# Connectors.net
KiCad netlist of a schematic drawn in Altium Designer
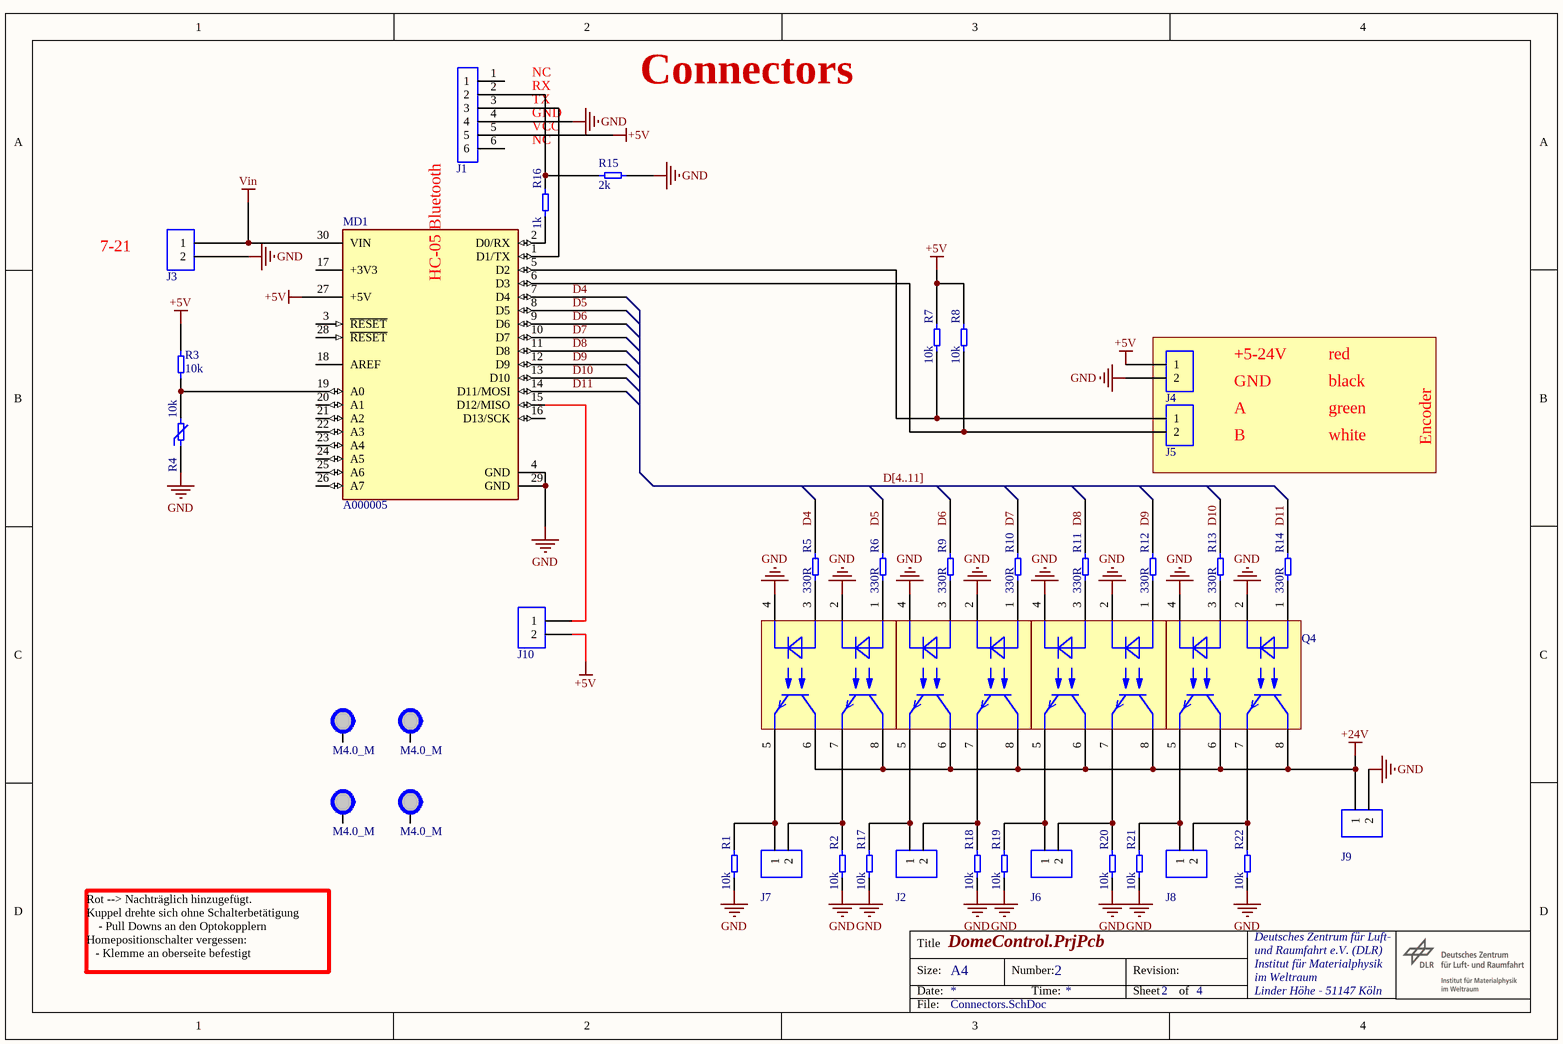
[diagram p0: Connectors.SchDoc]

(export (version "E")
  (design (tool "Eeschema 10.0.6"))
  (components
    (comp (ref "Drill1")
      (value "M4.0_M")
      (footprint "M4.0_M")
      (fields (field (name ".CHECKED PCB") "RF") (field (name ".CHECKED SCH") "RF"))
      (libsource (lib "Drills") (part "Drill"))
    )
    (comp (ref "Drill2")
      (value "M4.0_M")
      (footprint "M4.0_M")
      (fields (field (name ".CHECKED PCB") "RF") (field (name ".CHECKED SCH") "RF"))
      (libsource (lib "Drills") (part "Drill"))
    )
    (comp (ref "Drill3")
      (value "M4.0_M")
      (footprint "M4.0_M")
      (fields (field (name ".CHECKED PCB") "RF") (field (name ".CHECKED SCH") "RF"))
      (libsource (lib "Drills") (part "Drill"))
    )
    (comp (ref "Drill4")
      (value "M4.0_M")
      (footprint "M4.0_M")
      (fields (field (name ".CHECKED PCB") "RF") (field (name ".CHECKED SCH") "RF"))
      (libsource (lib "Drills") (part "Drill"))
    )
    (comp (ref "J1")
      (value "61300611121")
      (footprint "6P Stiftleiste 2,54")
      (fields
        (field (name "RS PART NUMBER") "172-5168")
        (field (name ".CHECKED PCB") "RF")
        (field (name ".CHECKED SCH") "RF")
      )
      (libsource (lib "EigenDefault") (part "6P Stiftleiste 2,54"))
    )
    (comp (ref "J2")
      (value "PM_5.08_3_90_3.5_SW_-176052000")
      (footprint "MKDSN 5,08/2 2,5")
      (description "间距5.08mm 2pin 10A 300V 可拼接 螺钉式 直插 配线24-14AWG(0.2-2.5)mm²")
      (fields
        (field (name "MANUFACTURER") "Phoenix Contact")
        (field (name "MANUFACTURER PART NUMBER") "1888687")
        (field (name ".CHECKED PCB") "PS")
        (field (name ".CHECKED SCH") "PS")
      )
      (libsource (lib "Phoenix Contact") (part "MKDSN 5,08/2 2,5"))
    )
    (comp (ref "J3")
      (value "PM_5.08_3_90_3.5_SW_-176052000")
      (footprint "MKDSN 5,08/2 2,5")
      (description "间距5.08mm 2pin 10A 300V 可拼接 螺钉式 直插 配线24-14AWG(0.2-2.5)mm²")
      (fields
        (field (name "MANUFACTURER") "Phoenix Contact")
        (field (name "MANUFACTURER PART NUMBER") "1888687")
        (field (name ".CHECKED PCB") "PS")
        (field (name ".CHECKED SCH") "PS")
      )
      (libsource (lib "Phoenix Contact") (part "MKDSN 5,08/2 2,5"))
    )
    (comp (ref "J4")
      (value "PM_5.08_3_90_3.5_SW_-176052000")
      (footprint "MKDSN 5,08/2 2,5")
      (description "间距5.08mm 2pin 10A 300V 可拼接 螺钉式 直插 配线24-14AWG(0.2-2.5)mm²")
      (fields
        (field (name "MANUFACTURER") "Phoenix Contact")
        (field (name "MANUFACTURER PART NUMBER") "1888687")
        (field (name ".CHECKED PCB") "PS")
        (field (name ".CHECKED SCH") "PS")
      )
      (libsource (lib "Phoenix Contact") (part "MKDSN 5,08/2 2,5"))
    )
    (comp (ref "J5")
      (value "PM_5.08_3_90_3.5_SW_-176052000")
      (footprint "MKDSN 5,08/2 2,5")
      (description "间距5.08mm 2pin 10A 300V 可拼接 螺钉式 直插 配线24-14AWG(0.2-2.5)mm²")
      (fields
        (field (name "MANUFACTURER") "Phoenix Contact")
        (field (name "MANUFACTURER PART NUMBER") "1888687")
        (field (name ".CHECKED PCB") "PS")
        (field (name ".CHECKED SCH") "PS")
      )
      (libsource (lib "Phoenix Contact") (part "MKDSN 5,08/2 2,5"))
    )
    (comp (ref "J6")
      (value "PM_5.08_3_90_3.5_SW_-176052000")
      (footprint "MKDSN 5,08/2 2,5")
      (description "间距5.08mm 2pin 10A 300V 可拼接 螺钉式 直插 配线24-14AWG(0.2-2.5)mm²")
      (fields
        (field (name "MANUFACTURER") "Phoenix Contact")
        (field (name "MANUFACTURER PART NUMBER") "1888687")
        (field (name ".CHECKED PCB") "PS")
        (field (name ".CHECKED SCH") "PS")
      )
      (libsource (lib "Phoenix Contact") (part "MKDSN 5,08/2 2,5"))
    )
    (comp (ref "J7")
      (value "PM_5.08_3_90_3.5_SW_-176052000")
      (footprint "MKDSN 5,08/2 2,5")
      (description "间距5.08mm 2pin 10A 300V 可拼接 螺钉式 直插 配线24-14AWG(0.2-2.5)mm²")
      (fields
        (field (name "MANUFACTURER") "Phoenix Contact")
        (field (name "MANUFACTURER PART NUMBER") "1888687")
        (field (name ".CHECKED PCB") "PS")
        (field (name ".CHECKED SCH") "PS")
      )
      (libsource (lib "Phoenix Contact") (part "MKDSN 5,08/2 2,5"))
    )
    (comp (ref "J8")
      (value "PM_5.08_3_90_3.5_SW_-176052000")
      (footprint "MKDSN 5,08/2 2,5")
      (description "间距5.08mm 2pin 10A 300V 可拼接 螺钉式 直插 配线24-14AWG(0.2-2.5)mm²")
      (fields
        (field (name "MANUFACTURER") "Phoenix Contact")
        (field (name "MANUFACTURER PART NUMBER") "1888687")
        (field (name ".CHECKED PCB") "PS")
        (field (name ".CHECKED SCH") "PS")
      )
      (libsource (lib "Phoenix Contact") (part "MKDSN 5,08/2 2,5"))
    )
    (comp (ref "J9")
      (value "PM_5.08_3_90_3.5_SW_-176052000")
      (footprint "MKDSN 5,08/2 2,5")
      (description "间距5.08mm 2pin 10A 300V 可拼接 螺钉式 直插 配线24-14AWG(0.2-2.5)mm²")
      (fields
        (field (name "MANUFACTURER") "Phoenix Contact")
        (field (name "MANUFACTURER PART NUMBER") "1888687")
        (field (name ".CHECKED PCB") "PS")
        (field (name ".CHECKED SCH") "PS")
      )
      (libsource (lib "Phoenix Contact") (part "MKDSN 5,08/2 2,5"))
    )
    (comp (ref "J10")
      (value "PM_5.08_3_90_3.5_SW_-176052000")
      (footprint "MKDSN 5,08/2 2,5")
      (description "间距5.08mm 2pin 10A 300V 可拼接 螺钉式 直插 配线24-14AWG(0.2-2.5)mm²")
      (fields
        (field (name "MANUFACTURER") "Phoenix Contact")
        (field (name "MANUFACTURER PART NUMBER") "1888687")
        (field (name ".CHECKED PCB") "PS")
        (field (name ".CHECKED SCH") "PS")
      )
      (libsource (lib "Phoenix Contact") (part "MKDSN 5,08/2 2,5"))
    )
    (comp (ref "MD1")
      (value "A000005")
      (footprint "FP-A000005-MFG")
      (description "ARDUINO NANO ATMEGA328 EVAL BRD")
      (libsource (lib "Altium Content Vault") (part "d190c066e99afd1c6882cf92e11b2cc"))
    )
    (comp (ref "Q1")
      (value "140827180010")
      (footprint "WL-OCPT_DIP8_Standard")
      (description "140827180010 WL-OCPT - Optocoupler Phototransistor")
      (libsource (lib "Altium Content Vault") (part "Optocoupler Phototransistor_DC_2 Channel"))
    )
    (comp (ref "Q2")
      (value "140827180010")
      (footprint "WL-OCPT_DIP8_Standard")
      (description "140827180010 WL-OCPT - Optocoupler Phototransistor")
      (libsource (lib "Altium Content Vault") (part "Optocoupler Phototransistor_DC_2 Channel"))
    )
    (comp (ref "Q3")
      (value "140827180010")
      (footprint "WL-OCPT_DIP8_Standard")
      (description "140827180010 WL-OCPT - Optocoupler Phototransistor")
      (libsource (lib "Altium Content Vault") (part "Optocoupler Phototransistor_DC_2 Channel"))
    )
    (comp (ref "Q4")
      (value "140827180010")
      (footprint "WL-OCPT_DIP8_Standard")
      (description "140827180010 WL-OCPT - Optocoupler Phototransistor")
      (libsource (lib "Altium Content Vault") (part "Optocoupler Phototransistor_DC_2 Channel"))
    )
    (comp (ref "R1")
      (value "10k")
      (footprint "Passive Bauelemente:laser AXIAL-0.5")
      (fields (field (name ".CHECKED PCB") "PS") (field (name ".CHECKED SCH") "PS"))
      (libsource (lib "Passive Bauelemente") (part "R-THT"))
    )
    (comp (ref "R2")
      (value "10k")
      (footprint "Passive Bauelemente:laser AXIAL-0.5")
      (fields (field (name ".CHECKED PCB") "PS") (field (name ".CHECKED SCH") "PS"))
      (libsource (lib "Passive Bauelemente") (part "R-THT"))
    )
    (comp (ref "R3")
      (value "10k")
      (footprint "Passive Bauelemente:laser AXIAL-0.5")
      (fields (field (name ".CHECKED PCB") "PS") (field (name ".CHECKED SCH") "PS"))
      (libsource (lib "Passive Bauelemente") (part "R-THT"))
    )
    (comp (ref "R4")
      (value "10k")
      (footprint "Passive Bauelemente:FP-103AT-2-MFG")
      (description "Thermistor NTC 10KOhm 1% 2-Pin\r\n103AT-2")
      (fields (field (name "TOLERANCE") "1%") (field (name "MANUFACTURER") "Semitec"))
      (libsource (lib "Passive Bauelemente") (part "R_Thermistor 2.54"))
    )
    (comp (ref "R5")
      (value "330R")
      (footprint "Passive Bauelemente:laser AXIAL-0.5")
      (fields (field (name ".CHECKED PCB") "PS") (field (name ".CHECKED SCH") "PS"))
      (libsource (lib "Passive Bauelemente") (part "R-THT"))
    )
    (comp (ref "R6")
      (value "330R")
      (footprint "Passive Bauelemente:laser AXIAL-0.5")
      (fields (field (name ".CHECKED PCB") "PS") (field (name ".CHECKED SCH") "PS"))
      (libsource (lib "Passive Bauelemente") (part "R-THT"))
    )
    (comp (ref "R7")
      (value "10k")
      (footprint "Passive Bauelemente:laser AXIAL-0.5")
      (fields (field (name ".CHECKED PCB") "PS") (field (name ".CHECKED SCH") "PS"))
      (libsource (lib "Passive Bauelemente") (part "R-THT"))
    )
    (comp (ref "R8")
      (value "10k")
      (footprint "Passive Bauelemente:laser AXIAL-0.5")
      (fields (field (name ".CHECKED PCB") "PS") (field (name ".CHECKED SCH") "PS"))
      (libsource (lib "Passive Bauelemente") (part "R-THT"))
    )
    (comp (ref "R9")
      (value "330R")
      (footprint "Passive Bauelemente:laser AXIAL-0.5")
      (fields (field (name ".CHECKED PCB") "PS") (field (name ".CHECKED SCH") "PS"))
      (libsource (lib "Passive Bauelemente") (part "R-THT"))
    )
    (comp (ref "R10")
      (value "330R")
      (footprint "Passive Bauelemente:laser AXIAL-0.5")
      (fields (field (name ".CHECKED PCB") "PS") (field (name ".CHECKED SCH") "PS"))
      (libsource (lib "Passive Bauelemente") (part "R-THT"))
    )
    (comp (ref "R11")
      (value "330R")
      (footprint "Passive Bauelemente:laser AXIAL-0.5")
      (fields (field (name ".CHECKED PCB") "PS") (field (name ".CHECKED SCH") "PS"))
      (libsource (lib "Passive Bauelemente") (part "R-THT"))
    )
    (comp (ref "R12")
      (value "330R")
      (footprint "Passive Bauelemente:laser AXIAL-0.5")
      (fields (field (name ".CHECKED PCB") "PS") (field (name ".CHECKED SCH") "PS"))
      (libsource (lib "Passive Bauelemente") (part "R-THT"))
    )
    (comp (ref "R13")
      (value "330R")
      (footprint "Passive Bauelemente:laser AXIAL-0.5")
      (fields (field (name ".CHECKED PCB") "PS") (field (name ".CHECKED SCH") "PS"))
      (libsource (lib "Passive Bauelemente") (part "R-THT"))
    )
    (comp (ref "R14")
      (value "330R")
      (footprint "Passive Bauelemente:laser AXIAL-0.5")
      (fields (field (name ".CHECKED PCB") "PS") (field (name ".CHECKED SCH") "PS"))
      (libsource (lib "Passive Bauelemente") (part "R-THT"))
    )
    (comp (ref "R15")
      (value "2k")
      (footprint "Passive Bauelemente:laser AXIAL-0.5")
      (fields (field (name ".CHECKED PCB") "PS") (field (name ".CHECKED SCH") "PS"))
      (libsource (lib "Passive Bauelemente") (part "R-THT"))
    )
    (comp (ref "R16")
      (value "1k")
      (footprint "Passive Bauelemente:laser AXIAL-0.5")
      (fields (field (name ".CHECKED PCB") "PS") (field (name ".CHECKED SCH") "PS"))
      (libsource (lib "Passive Bauelemente") (part "R-THT"))
    )
    (comp (ref "R17")
      (value "10k")
      (footprint "Passive Bauelemente:laser AXIAL-0.5")
      (fields (field (name ".CHECKED PCB") "PS") (field (name ".CHECKED SCH") "PS"))
      (libsource (lib "Passive Bauelemente") (part "R-THT"))
    )
    (comp (ref "R18")
      (value "10k")
      (footprint "Passive Bauelemente:laser AXIAL-0.5")
      (fields (field (name ".CHECKED PCB") "PS") (field (name ".CHECKED SCH") "PS"))
      (libsource (lib "Passive Bauelemente") (part "R-THT"))
    )
    (comp (ref "R19")
      (value "10k")
      (footprint "Passive Bauelemente:laser AXIAL-0.5")
      (fields (field (name ".CHECKED PCB") "PS") (field (name ".CHECKED SCH") "PS"))
      (libsource (lib "Passive Bauelemente") (part "R-THT"))
    )
    (comp (ref "R20")
      (value "10k")
      (footprint "Passive Bauelemente:laser AXIAL-0.5")
      (fields (field (name ".CHECKED PCB") "PS") (field (name ".CHECKED SCH") "PS"))
      (libsource (lib "Passive Bauelemente") (part "R-THT"))
    )
    (comp (ref "R21")
      (value "10k")
      (footprint "Passive Bauelemente:laser AXIAL-0.5")
      (fields (field (name ".CHECKED PCB") "PS") (field (name ".CHECKED SCH") "PS"))
      (libsource (lib "Passive Bauelemente") (part "R-THT"))
    )
    (comp (ref "R22")
      (value "10k")
      (footprint "Passive Bauelemente:laser AXIAL-0.5")
      (fields (field (name ".CHECKED PCB") "PS") (field (name ".CHECKED SCH") "PS"))
      (libsource (lib "Passive Bauelemente") (part "R-THT"))
    )
  )
  (nets
    (net (code "1") (name "+5V") (class "Default")
      (node (ref "J1") (pin "5") (pinfunction "5_5") (pintype "passive"))
      (node (ref "J10") (pin "2") (pinfunction "2_2") (pintype "passive"))
      (node (ref "J4") (pin "1") (pinfunction "1_1") (pintype "passive"))
      (node (ref "MD1") (pin "27") (pinfunction "+5V_27") (pintype "power_in"))
      (node (ref "R3") (pin "2") (pinfunction "2_2") (pintype "passive"))
      (node (ref "R7") (pin "1") (pinfunction "1_1") (pintype "passive"))
      (node (ref "R8") (pin "1") (pinfunction "1_1") (pintype "passive"))
    )
    (net (code "2") (name "+24V") (class "Default")
      (node (ref "J9") (pin "1") (pinfunction "1_1") (pintype "passive"))
      (node (ref "Q1") (pin "6") (pinfunction "Collector_6") (pintype "passive"))
      (node (ref "Q1") (pin "8") (pinfunction "Collector_8") (pintype "passive"))
      (node (ref "Q2") (pin "6") (pinfunction "Collector_6") (pintype "passive"))
      (node (ref "Q2") (pin "8") (pinfunction "Collector_8") (pintype "passive"))
      (node (ref "Q3") (pin "6") (pinfunction "Collector_6") (pintype "passive"))
      (node (ref "Q3") (pin "8") (pinfunction "Collector_8") (pintype "passive"))
      (node (ref "Q4") (pin "6") (pinfunction "Collector_6") (pintype "passive"))
      (node (ref "Q4") (pin "8") (pinfunction "Collector_8") (pintype "passive"))
    )
    (net (code "3") (name "/D4") (class "Default")
      (node (ref "MD1") (pin "7") (pinfunction "D4_7") (pintype "bidirectional"))
      (node (ref "R5") (pin "1") (pinfunction "1_1") (pintype "passive"))
    )
    (net (code "4") (name "/D5") (class "Default")
      (node (ref "MD1") (pin "8") (pinfunction "D5_8") (pintype "bidirectional"))
      (node (ref "R6") (pin "1") (pinfunction "1_1") (pintype "passive"))
    )
    (net (code "5") (name "/D6") (class "Default")
      (node (ref "MD1") (pin "9") (pinfunction "D6_9") (pintype "bidirectional"))
      (node (ref "R9") (pin "1") (pinfunction "1_1") (pintype "passive"))
    )
    (net (code "6") (name "/D7") (class "Default")
      (node (ref "MD1") (pin "10") (pinfunction "D7_10") (pintype "bidirectional"))
      (node (ref "R10") (pin "1") (pinfunction "1_1") (pintype "passive"))
    )
    (net (code "7") (name "/D8") (class "Default")
      (node (ref "MD1") (pin "11") (pinfunction "D8_11") (pintype "bidirectional"))
      (node (ref "R11") (pin "1") (pinfunction "1_1") (pintype "passive"))
    )
    (net (code "8") (name "/D9") (class "Default")
      (node (ref "MD1") (pin "12") (pinfunction "D9_12") (pintype "bidirectional"))
      (node (ref "R12") (pin "1") (pinfunction "1_1") (pintype "passive"))
    )
    (net (code "9") (name "/D10") (class "Default")
      (node (ref "MD1") (pin "13") (pinfunction "D10_13") (pintype "bidirectional"))
      (node (ref "R13") (pin "1") (pinfunction "1_1") (pintype "passive"))
    )
    (net (code "10") (name "/D11") (class "Default")
      (node (ref "MD1") (pin "14") (pinfunction "D11/MOSI_14") (pintype "bidirectional"))
      (node (ref "R14") (pin "1") (pinfunction "1_1") (pintype "passive"))
    )
    (net (code "12") (name "GND") (class "Default")
      (node (ref "J1") (pin "4") (pinfunction "4_4") (pintype "passive"))
      (node (ref "J3") (pin "2") (pinfunction "2_2") (pintype "passive"))
      (node (ref "J4") (pin "2") (pinfunction "2_2") (pintype "passive"))
      (node (ref "J9") (pin "2") (pinfunction "2_2") (pintype "passive"))
      (node (ref "MD1") (pin "29") (pinfunction "GND_29") (pintype "power_in"))
      (node (ref "MD1") (pin "4") (pinfunction "GND_4") (pintype "power_in"))
      (node (ref "Q1") (pin "2") (pinfunction "Cathode_2") (pintype "passive"))
      (node (ref "Q1") (pin "4") (pinfunction "Cathode_4") (pintype "passive"))
      (node (ref "Q2") (pin "2") (pinfunction "Cathode_2") (pintype "passive"))
      (node (ref "Q2") (pin "4") (pinfunction "Cathode_4") (pintype "passive"))
      (node (ref "Q3") (pin "2") (pinfunction "Cathode_2") (pintype "passive"))
      (node (ref "Q3") (pin "4") (pinfunction "Cathode_4") (pintype "passive"))
      (node (ref "Q4") (pin "2") (pinfunction "Cathode_2") (pintype "passive"))
      (node (ref "Q4") (pin "4") (pinfunction "Cathode_4") (pintype "passive"))
      (node (ref "R1") (pin "2") (pinfunction "2_2") (pintype "passive"))
      (node (ref "R15") (pin "2") (pinfunction "2_2") (pintype "passive"))
      (node (ref "R17") (pin "2") (pinfunction "2_2") (pintype "passive"))
      (node (ref "R18") (pin "2") (pinfunction "2_2") (pintype "passive"))
      (node (ref "R19") (pin "2") (pinfunction "2_2") (pintype "passive"))
      (node (ref "R2") (pin "2") (pinfunction "2_2") (pintype "passive"))
      (node (ref "R20") (pin "2") (pinfunction "2_2") (pintype "passive"))
      (node (ref "R21") (pin "2") (pinfunction "2_2") (pintype "passive"))
      (node (ref "R22") (pin "2") (pinfunction "2_2") (pintype "passive"))
      (node (ref "R4") (pin "1") (pinfunction "1_1") (pintype "passive"))
    )
    (net (code "13") (name "Net-(J1-Pad2)") (class "Default")
      (node (ref "J1") (pin "2") (pinfunction "2_2") (pintype "passive"))
      (node (ref "R15") (pin "1") (pinfunction "1_1") (pintype "passive"))
      (node (ref "R16") (pin "2") (pinfunction "2_2") (pintype "passive"))
    )
    (net (code "14") (name "Net-(J2-Pad1)") (class "Default")
      (node (ref "J2") (pin "1") (pinfunction "1_1") (pintype "passive"))
      (node (ref "Q2") (pin "5") (pinfunction "Emitter_5") (pintype "passive"))
      (node (ref "R17") (pin "1") (pinfunction "1_1") (pintype "passive"))
    )
    (net (code "15") (name "Net-(J2-Pad2)") (class "Default")
      (node (ref "J2") (pin "2") (pinfunction "2_2") (pintype "passive"))
      (node (ref "Q2") (pin "7") (pinfunction "Emitter_7") (pintype "passive"))
      (node (ref "R18") (pin "1") (pinfunction "1_1") (pintype "passive"))
    )
    (net (code "16") (name "Net-(J6-Pad1)") (class "Default")
      (node (ref "J6") (pin "1") (pinfunction "1_1") (pintype "passive"))
      (node (ref "Q3") (pin "5") (pinfunction "Emitter_5") (pintype "passive"))
      (node (ref "R19") (pin "1") (pinfunction "1_1") (pintype "passive"))
    )
    (net (code "17") (name "Net-(J6-Pad2)") (class "Default")
      (node (ref "J6") (pin "2") (pinfunction "2_2") (pintype "passive"))
      (node (ref "Q3") (pin "7") (pinfunction "Emitter_7") (pintype "passive"))
      (node (ref "R20") (pin "1") (pinfunction "1_1") (pintype "passive"))
    )
    (net (code "18") (name "Net-(J7-Pad1)") (class "Default")
      (node (ref "J7") (pin "1") (pinfunction "1_1") (pintype "passive"))
      (node (ref "Q1") (pin "5") (pinfunction "Emitter_5") (pintype "passive"))
      (node (ref "R1") (pin "1") (pinfunction "1_1") (pintype "passive"))
    )
    (net (code "19") (name "Net-(J7-Pad2)") (class "Default")
      (node (ref "J7") (pin "2") (pinfunction "2_2") (pintype "passive"))
      (node (ref "Q1") (pin "7") (pinfunction "Emitter_7") (pintype "passive"))
      (node (ref "R2") (pin "1") (pinfunction "1_1") (pintype "passive"))
    )
    (net (code "20") (name "Net-(J8-Pad1)") (class "Default")
      (node (ref "J8") (pin "1") (pinfunction "1_1") (pintype "passive"))
      (node (ref "Q4") (pin "5") (pinfunction "Emitter_5") (pintype "passive"))
      (node (ref "R21") (pin "1") (pinfunction "1_1") (pintype "passive"))
    )
    (net (code "21") (name "Net-(J8-Pad2)") (class "Default")
      (node (ref "J8") (pin "2") (pinfunction "2_2") (pintype "passive"))
      (node (ref "Q4") (pin "7") (pinfunction "Emitter_7") (pintype "passive"))
      (node (ref "R22") (pin "1") (pinfunction "1_1") (pintype "passive"))
    )
    (net (code "22") (name "Net-(MD1-A0)") (class "Default")
      (node (ref "MD1") (pin "19") (pinfunction "A0_19") (pintype "bidirectional"))
      (node (ref "R3") (pin "1") (pinfunction "1_1") (pintype "passive"))
      (node (ref "R4") (pin "2") (pinfunction "2_2") (pintype "passive"))
    )
    (net (code "23") (name "Net-(MD1-D0{slash}RX)") (class "Default")
      (node (ref "MD1") (pin "2") (pinfunction "D0/RX_2") (pintype "bidirectional"))
      (node (ref "R16") (pin "1") (pinfunction "1_1") (pintype "passive"))
    )
    (net (code "24") (name "Net-(MD1-D1{slash}TX)") (class "Default")
      (node (ref "J1") (pin "3") (pinfunction "3_3") (pintype "passive"))
      (node (ref "MD1") (pin "1") (pinfunction "D1/TX_1") (pintype "bidirectional"))
    )
    (net (code "25") (name "Net-(MD1-D2)") (class "Default")
      (node (ref "J5") (pin "1") (pinfunction "1_1") (pintype "passive"))
      (node (ref "MD1") (pin "5") (pinfunction "D2_5") (pintype "bidirectional"))
      (node (ref "R7") (pin "2") (pinfunction "2_2") (pintype "passive"))
    )
    (net (code "26") (name "Net-(MD1-D3)") (class "Default")
      (node (ref "J5") (pin "2") (pinfunction "2_2") (pintype "passive"))
      (node (ref "MD1") (pin "6") (pinfunction "D3_6") (pintype "bidirectional"))
      (node (ref "R8") (pin "2") (pinfunction "2_2") (pintype "passive"))
    )
    (net (code "27") (name "Net-(MD1-D12{slash}MISO)") (class "Default")
      (node (ref "J10") (pin "1") (pinfunction "1_1") (pintype "passive"))
      (node (ref "MD1") (pin "15") (pinfunction "D12/MISO_15") (pintype "bidirectional"))
    )
    (net (code "28") (name "Net-(Q1-Anode-Pad1)") (class "Default")
      (node (ref "Q1") (pin "1") (pinfunction "Anode_1") (pintype "passive"))
      (node (ref "R6") (pin "2") (pinfunction "2_2") (pintype "passive"))
    )
    (net (code "29") (name "Net-(Q1-Anode-Pad3)") (class "Default")
      (node (ref "Q1") (pin "3") (pinfunction "Anode_3") (pintype "passive"))
      (node (ref "R5") (pin "2") (pinfunction "2_2") (pintype "passive"))
    )
    (net (code "30") (name "Net-(Q2-Anode-Pad1)") (class "Default")
      (node (ref "Q2") (pin "1") (pinfunction "Anode_1") (pintype "passive"))
      (node (ref "R10") (pin "2") (pinfunction "2_2") (pintype "passive"))
    )
    (net (code "31") (name "Net-(Q2-Anode-Pad3)") (class "Default")
      (node (ref "Q2") (pin "3") (pinfunction "Anode_3") (pintype "passive"))
      (node (ref "R9") (pin "2") (pinfunction "2_2") (pintype "passive"))
    )
    (net (code "32") (name "Net-(Q3-Anode-Pad1)") (class "Default")
      (node (ref "Q3") (pin "1") (pinfunction "Anode_1") (pintype "passive"))
      (node (ref "R12") (pin "2") (pinfunction "2_2") (pintype "passive"))
    )
    (net (code "33") (name "Net-(Q3-Anode-Pad3)") (class "Default")
      (node (ref "Q3") (pin "3") (pinfunction "Anode_3") (pintype "passive"))
      (node (ref "R11") (pin "2") (pinfunction "2_2") (pintype "passive"))
    )
    (net (code "34") (name "Net-(Q4-Anode-Pad1)") (class "Default")
      (node (ref "Q4") (pin "1") (pinfunction "Anode_1") (pintype "passive"))
      (node (ref "R14") (pin "2") (pinfunction "2_2") (pintype "passive"))
    )
    (net (code "35") (name "Net-(Q4-Anode-Pad3)") (class "Default")
      (node (ref "Q4") (pin "3") (pinfunction "Anode_3") (pintype "passive"))
      (node (ref "R13") (pin "2") (pinfunction "2_2") (pintype "passive"))
    )
    (net (code "36") (name "Vin") (class "Default")
      (node (ref "J3") (pin "1") (pinfunction "1_1") (pintype "passive"))
      (node (ref "MD1") (pin "30") (pinfunction "VIN_30") (pintype "power_in"))
    )
    (net (code "37") (name "unconnected-(Drill1-Pad1)") (class "Default")
      (node (ref "Drill1") (pin "1") (pinfunction "1_1") (pintype "passive"))
    )
    (net (code "38") (name "unconnected-(Drill2-Pad1)") (class "Default")
      (node (ref "Drill2") (pin "1") (pinfunction "1_1") (pintype "passive"))
    )
    (net (code "39") (name "unconnected-(Drill3-Pad1)") (class "Default")
      (node (ref "Drill3") (pin "1") (pinfunction "1_1") (pintype "passive"))
    )
    (net (code "40") (name "unconnected-(Drill4-Pad1)") (class "Default")
      (node (ref "Drill4") (pin "1") (pinfunction "1_1") (pintype "passive"))
    )
    (net (code "41") (name "unconnected-(J1-Pad1)") (class "Default")
      (node (ref "J1") (pin "1") (pinfunction "1_1") (pintype "passive"))
    )
    (net (code "42") (name "unconnected-(J1-Pad6)") (class "Default")
      (node (ref "J1") (pin "6") (pinfunction "6_6") (pintype "passive"))
    )
    (net (code "43") (name "unconnected-(MD1-+3V3-Pad17)") (class "Default")
      (node (ref "MD1") (pin "17") (pinfunction "+3V3_17") (pintype "power_in"))
    )
    (net (code "44") (name "unconnected-(MD1-A1-Pad20)") (class "Default")
      (node (ref "MD1") (pin "20") (pinfunction "A1_20") (pintype "bidirectional"))
    )
    (net (code "45") (name "unconnected-(MD1-A2-Pad21)") (class "Default")
      (node (ref "MD1") (pin "21") (pinfunction "A2_21") (pintype "bidirectional"))
    )
    (net (code "46") (name "unconnected-(MD1-A3-Pad22)") (class "Default")
      (node (ref "MD1") (pin "22") (pinfunction "A3_22") (pintype "bidirectional"))
    )
    (net (code "47") (name "unconnected-(MD1-A4-Pad23)") (class "Default")
      (node (ref "MD1") (pin "23") (pinfunction "A4_23") (pintype "bidirectional"))
    )
    (net (code "48") (name "unconnected-(MD1-A5-Pad24)") (class "Default")
      (node (ref "MD1") (pin "24") (pinfunction "A5_24") (pintype "bidirectional"))
    )
    (net (code "49") (name "unconnected-(MD1-A6-Pad25)") (class "Default")
      (node (ref "MD1") (pin "25") (pinfunction "A6_25") (pintype "bidirectional"))
    )
    (net (code "50") (name "unconnected-(MD1-A7-Pad26)") (class "Default")
      (node (ref "MD1") (pin "26") (pinfunction "A7_26") (pintype "bidirectional"))
    )
    (net (code "51") (name "unconnected-(MD1-AREF-Pad18)") (class "Default")
      (node (ref "MD1") (pin "18") (pinfunction "AREF_18") (pintype "passive"))
    )
    (net (code "52") (name "unconnected-(MD1-D13{slash}SCK-Pad16)") (class "Default")
      (node (ref "MD1") (pin "16") (pinfunction "D13/SCK_16") (pintype "bidirectional"))
    )
    (net (code "53") (name "unconnected-(MD1-~{RESET}-Pad3)") (class "Default")
      (node (ref "MD1") (pin "3") (pinfunction "~{RESET}_3") (pintype "input"))
    )
    (net (code "54") (name "unconnected-(MD1-~{RESET}-Pad28)") (class "Default")
      (node (ref "MD1") (pin "28") (pinfunction "~{RESET}_28") (pintype "input"))
    )
  )
)
